# reload.net
KiCad netlist of a schematic drawn in EAGLE
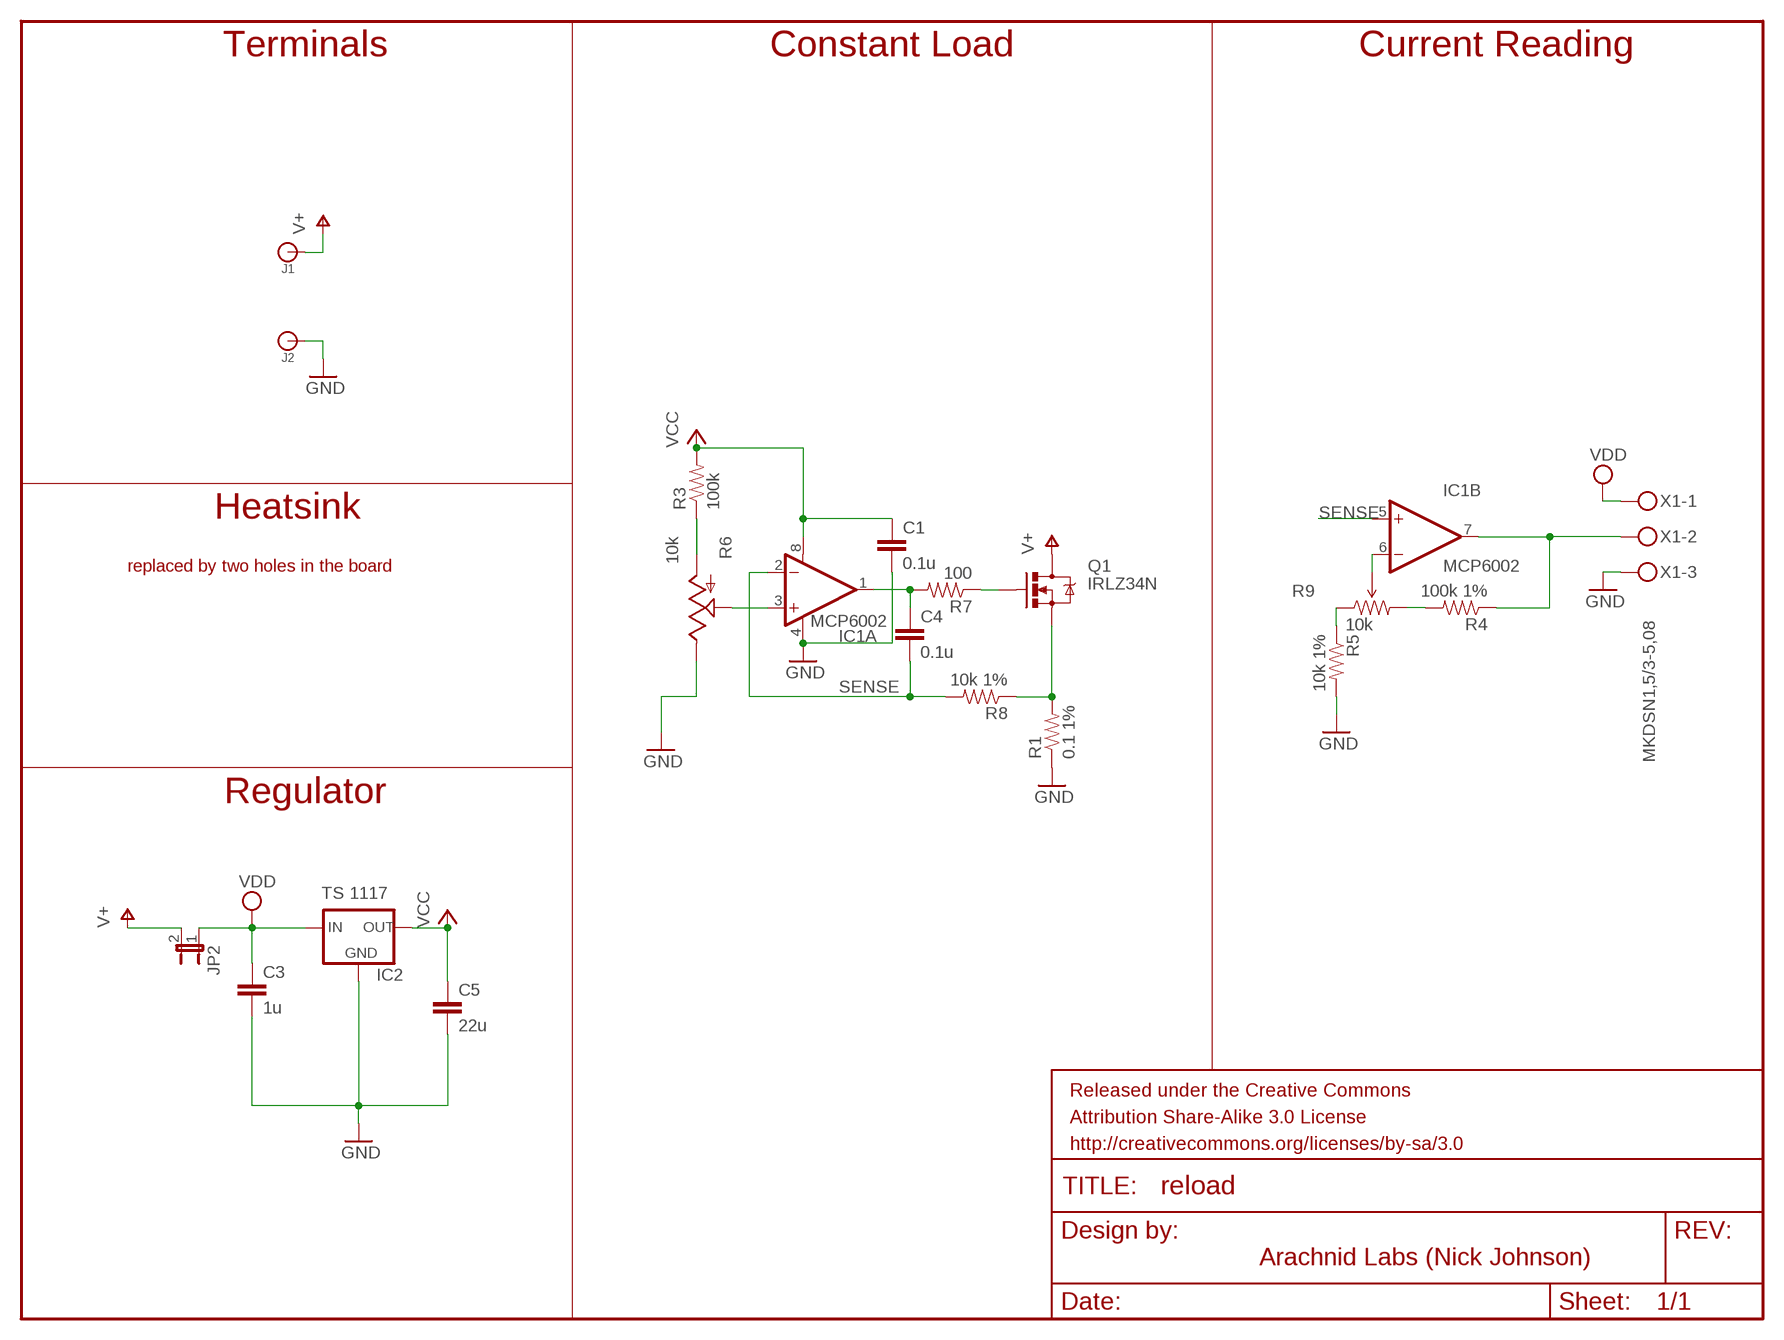
[diagram p0: schematic, sheet 1]

(export (version "E")
  (design (tool "Eeschema 10.0.6"))
  (components
    (comp (ref "C1")
      (value "0.1u")
      (footprint "eagle-import:0805")
      (libsource (lib "eagle-import") (part "CAP0805"))
    )
    (comp (ref "C3")
      (value "1u")
      (footprint "eagle-import:0805")
      (libsource (lib "eagle-import") (part "CAP0805"))
    )
    (comp (ref "C4")
      (value "0.1u")
      (footprint "eagle-import:0805")
      (libsource (lib "eagle-import") (part "CAP0805"))
    )
    (comp (ref "C5")
      (value "22u")
      (footprint "eagle-import:0805")
      (libsource (lib "eagle-import") (part "CAP0805"))
    )
    (comp (ref "IC1")
      (value "MCP6002")
      (footprint "eagle-import:SOP08")
      (libsource (lib "eagle-import") (part "OPAMP-DUALMS"))
    )
    (comp (ref "IC2")
      (value "TS 1117")
      (footprint "eagle-import:SOT223")
      (libsource (lib "eagle-import") (part "V_REG_MIC2920"))
    )
    (comp (ref "J1")
      (value "BANANA_CONN")
      (footprint "eagle-import:BANANA_CONN")
      (libsource (lib "eagle-import") (part "BANANA_CONN"))
    )
    (comp (ref "J2")
      (value "BANANA_CONN")
      (footprint "eagle-import:BANANA_CONN")
      (libsource (lib "eagle-import") (part "BANANA_CONN"))
    )
    (comp (ref "JP2")
      (value "JUMPER-2PTH")
      (footprint "eagle-import:1X02")
      (libsource (lib "eagle-import") (part "JUMPER-2PTH"))
    )
    (comp (ref "Q1")
      (value "IRLZ34N")
      (footprint "eagle-import:TO220V")
      (libsource (lib "eagle-import") (part "MOSFET-NCHANNELPTH2"))
    )
    (comp (ref "R1")
      (value "0.1 1%")
      (footprint "eagle-import:R2512")
      (libsource (lib "eagle-import") (part "RESISTOR2512"))
    )
    (comp (ref "R3")
      (value "100k")
      (footprint "eagle-import:0805")
      (libsource (lib "eagle-import") (part "RESISTOR0805-RES"))
    )
    (comp (ref "R4")
      (value "100k 1%")
      (footprint "eagle-import:0805")
      (libsource (lib "eagle-import") (part "RESISTOR0805-RES"))
    )
    (comp (ref "R5")
      (value "10k 1%")
      (footprint "eagle-import:0805")
      (libsource (lib "eagle-import") (part "RESISTOR0805-RES"))
    )
    (comp (ref "R6")
      (value "10k")
      (footprint "eagle-import:ALPS_POT")
      (libsource (lib "eagle-import") (part "POT"))
    )
    (comp (ref "R7")
      (value "100")
      (footprint "eagle-import:0805")
      (libsource (lib "eagle-import") (part "RESISTOR0805-RES"))
    )
    (comp (ref "R8")
      (value "10k 1%")
      (footprint "eagle-import:0805")
      (libsource (lib "eagle-import") (part "RESISTOR0805-RES"))
    )
    (comp (ref "R9")
      (value "10k")
      (footprint "eagle-import:TRIMPOT-5MM")
      (libsource (lib "eagle-import") (part "TRIMPOTTS53YJ"))
    )
    (comp (ref "X1")
      (value "MKDSN1,5/3-5,08")
      (footprint "eagle-import:MKDSN1,5_3-5,08")
      (fields (field (name "MPN") "SMKDSN1,5/3-5,08"))
      (libsource (lib "eagle-import") (part "MKDSN1,5/3-5,08"))
    )
  )
  (nets
    (net (code "1") (name "/SENSE") (class "Default")
      (node (ref "C4") (pin "2") (pinfunction "2_2") (pintype "passive"))
      (node (ref "IC1") (pin "2") (pinfunction "-IN_2") (pintype "input"))
      (node (ref "IC1") (pin "5") (pinfunction "+IN_5") (pintype "input"))
      (node (ref "R8") (pin "2") (pinfunction "2_2") (pintype "passive"))
    )
    (net (code "2") (name "GND") (class "Default")
      (node (ref "C1") (pin "2") (pinfunction "2_2") (pintype "passive"))
      (node (ref "C3") (pin "2") (pinfunction "2_2") (pintype "passive"))
      (node (ref "C5") (pin "2") (pinfunction "2_2") (pintype "passive"))
      (node (ref "IC1") (pin "4") (pinfunction "V-_4") (pintype "power_in"))
      (node (ref "IC2") (pin "2") (pinfunction "GND_2") (pintype "input"))
      (node (ref "J2") (pin "P$1") (pinfunction "1_P$1") (pintype "passive"))
      (node (ref "R1") (pin "1") (pinfunction "1_1") (pintype "passive"))
      (node (ref "R5") (pin "2") (pinfunction "2_2") (pintype "passive"))
      (node (ref "R6") (pin "P$1") (pinfunction "E_P$1") (pintype "passive"))
      (node (ref "X1") (pin "3") (pinfunction "KL_3") (pintype "passive"))
    )
    (net (code "3") (name "Net-(IC1A-+IN)") (class "Default")
      (node (ref "IC1") (pin "3") (pinfunction "+IN_3") (pintype "input"))
      (node (ref "R6") (pin "P$2") (pinfunction "S_P$2") (pintype "passive"))
    )
    (net (code "4") (name "Net-(IC1A-OUT)") (class "Default")
      (node (ref "C4") (pin "1") (pinfunction "1_1") (pintype "passive"))
      (node (ref "IC1") (pin "1") (pinfunction "OUT_1") (pintype "output"))
      (node (ref "R7") (pin "2") (pinfunction "2_2") (pintype "passive"))
    )
    (net (code "5") (name "Net-(IC1B--IN)") (class "Default")
      (node (ref "IC1") (pin "6") (pinfunction "-IN_6") (pintype "input"))
      (node (ref "R9") (pin "B") (pinfunction "WIPER_B") (pintype "passive"))
    )
    (net (code "6") (name "Net-(IC1B-OUT)") (class "Default")
      (node (ref "IC1") (pin "7") (pinfunction "OUT_7") (pintype "output"))
      (node (ref "R4") (pin "1") (pinfunction "1_1") (pintype "passive"))
      (node (ref "X1") (pin "2") (pinfunction "KL_2") (pintype "passive"))
    )
    (net (code "7") (name "Net-(Q1-G)") (class "Default")
      (node (ref "Q1") (pin "1") (pinfunction "G_1") (pintype "passive"))
      (node (ref "R7") (pin "1") (pinfunction "1_1") (pintype "passive"))
    )
    (net (code "8") (name "Net-(Q1-S)") (class "Default")
      (node (ref "Q1") (pin "3") (pinfunction "S_3") (pintype "passive"))
      (node (ref "R1") (pin "2") (pinfunction "2_2") (pintype "passive"))
      (node (ref "R8") (pin "1") (pinfunction "1_1") (pintype "passive"))
    )
    (net (code "9") (name "Net-(R6-A)") (class "Default")
      (node (ref "R3") (pin "1") (pinfunction "1_1") (pintype "passive"))
      (node (ref "R6") (pin "P$3") (pinfunction "A_P$3") (pintype "passive"))
    )
    (net (code "10") (name "Net-(R9-CCW)") (class "Default")
      (node (ref "R5") (pin "1") (pinfunction "1_1") (pintype "passive"))
      (node (ref "R9") (pin "A") (pinfunction "CCW_A") (pintype "passive"))
    )
    (net (code "11") (name "Net-(R9-CW)") (class "Default")
      (node (ref "R4") (pin "2") (pinfunction "2_2") (pintype "passive"))
      (node (ref "R9") (pin "C") (pinfunction "CW_C") (pintype "passive"))
    )
    (net (code "12") (name "V+") (class "Default")
      (node (ref "J1") (pin "P$1") (pinfunction "1_P$1") (pintype "passive"))
      (node (ref "JP2") (pin "2") (pinfunction "2_2") (pintype "passive"))
      (node (ref "Q1") (pin "2") (pinfunction "D_2") (pintype "passive"))
    )
    (net (code "13") (name "VCC") (class "Default")
      (node (ref "C1") (pin "1") (pinfunction "1_1") (pintype "passive"))
      (node (ref "C5") (pin "1") (pinfunction "1_1") (pintype "passive"))
      (node (ref "IC1") (pin "8") (pinfunction "V+_8") (pintype "power_in"))
      (node (ref "IC2") (pin "3") (pinfunction "OUT_3") (pintype "output"))
      (node (ref "R3") (pin "2") (pinfunction "2_2") (pintype "passive"))
    )
    (net (code "14") (name "VDD") (class "Default")
      (node (ref "C3") (pin "1") (pinfunction "1_1") (pintype "passive"))
      (node (ref "IC2") (pin "1") (pinfunction "IN_1") (pintype "input"))
      (node (ref "JP2") (pin "1") (pinfunction "1_1") (pintype "passive"))
      (node (ref "X1") (pin "1") (pinfunction "KL_1") (pintype "passive"))
    )
  )
)
